# Mechanical.net
KiCad netlist of a schematic drawn in Altium Designer
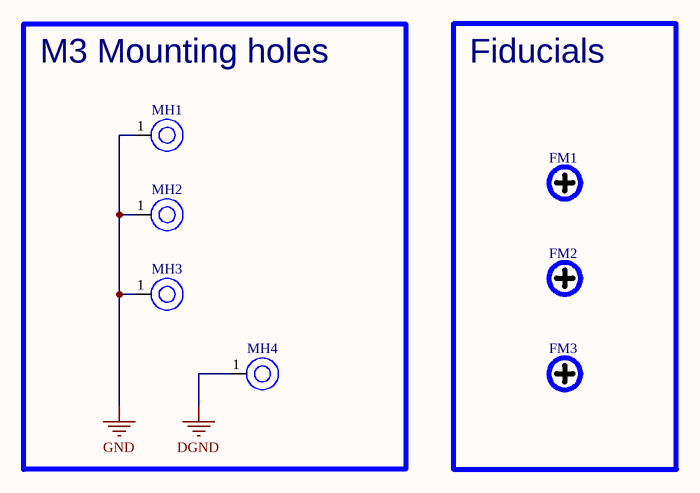
[diagram p0: Mechanical.SchDoc]

(export (version "E")
  (design (tool "Eeschema 10.0.6"))
  (components
    (comp (ref "FM1")
      (value "FIDUCIAL_CROSS_1MM5")
      (footprint "FIDUCIAL_CROSS_1MM5")
      (description "Fiducial Marker Cross 1.5mm NO BOM")
      (fields (field (name "SOURCE") "Schematic-Lib-PhilsLab.SchLib"))
      (libsource (lib "Leonhard Waibl") (part "FIDUCIAL_CROSS_1MM5"))
    )
    (comp (ref "FM2")
      (value "FIDUCIAL_CROSS_1MM5")
      (footprint "FIDUCIAL_CROSS_1MM5")
      (description "Fiducial Marker Cross 1.5mm NO BOM")
      (fields (field (name "SOURCE") "Schematic-Lib-PhilsLab.SchLib"))
      (libsource (lib "Leonhard Waibl") (part "FIDUCIAL_CROSS_1MM5"))
    )
    (comp (ref "FM3")
      (value "FIDUCIAL_CROSS_1MM5")
      (footprint "FIDUCIAL_CROSS_1MM5")
      (description "Fiducial Marker Cross 1.5mm NO BOM")
      (fields (field (name "SOURCE") "Schematic-Lib-PhilsLab.SchLib"))
      (libsource (lib "Leonhard Waibl") (part "FIDUCIAL_CROSS_1MM5"))
    )
    (comp (ref "MH1")
      (value "MTHP3P2MM")
      (footprint "MTHP3P2MM-Footprint-1")
      (description "Mounting Hole Plated 3.2 mm drill")
      (libsource (lib "Leonhard Waibl") (part "MTHP3P2MM"))
    )
    (comp (ref "MH2")
      (value "MTHP3P2MM")
      (footprint "MTHP3P2MM-Footprint-1")
      (description "Mounting Hole Plated 3.2 mm drill")
      (libsource (lib "Leonhard Waibl") (part "MTHP3P2MM"))
    )
    (comp (ref "MH3")
      (value "MTHP3P2MM")
      (footprint "MTHP3P2MM-Footprint-1")
      (description "Mounting Hole Plated 3.2 mm drill")
      (libsource (lib "Leonhard Waibl") (part "MTHP3P2MM"))
    )
    (comp (ref "MH4")
      (value "MTHP3P2MM")
      (footprint "MTHP3P2MM-Footprint-1")
      (description "Mounting Hole Plated 3.2 mm drill")
      (libsource (lib "Leonhard Waibl") (part "MTHP3P2MM"))
    )
  )
  (nets
    (net (code "1") (name "DGND") (class "Default")
      (node (ref "MH4") (pin "1") (pinfunction "1_1") (pintype "passive"))
    )
    (net (code "2") (name "GND") (class "Default")
      (node (ref "MH1") (pin "1") (pinfunction "1_1") (pintype "passive"))
      (node (ref "MH2") (pin "1") (pinfunction "1_1") (pintype "passive"))
      (node (ref "MH3") (pin "1") (pinfunction "1_1") (pintype "passive"))
    )
  )
)
